# CAN-D_Rev2.net
KiCad netlist of a schematic drawn in EAGLE
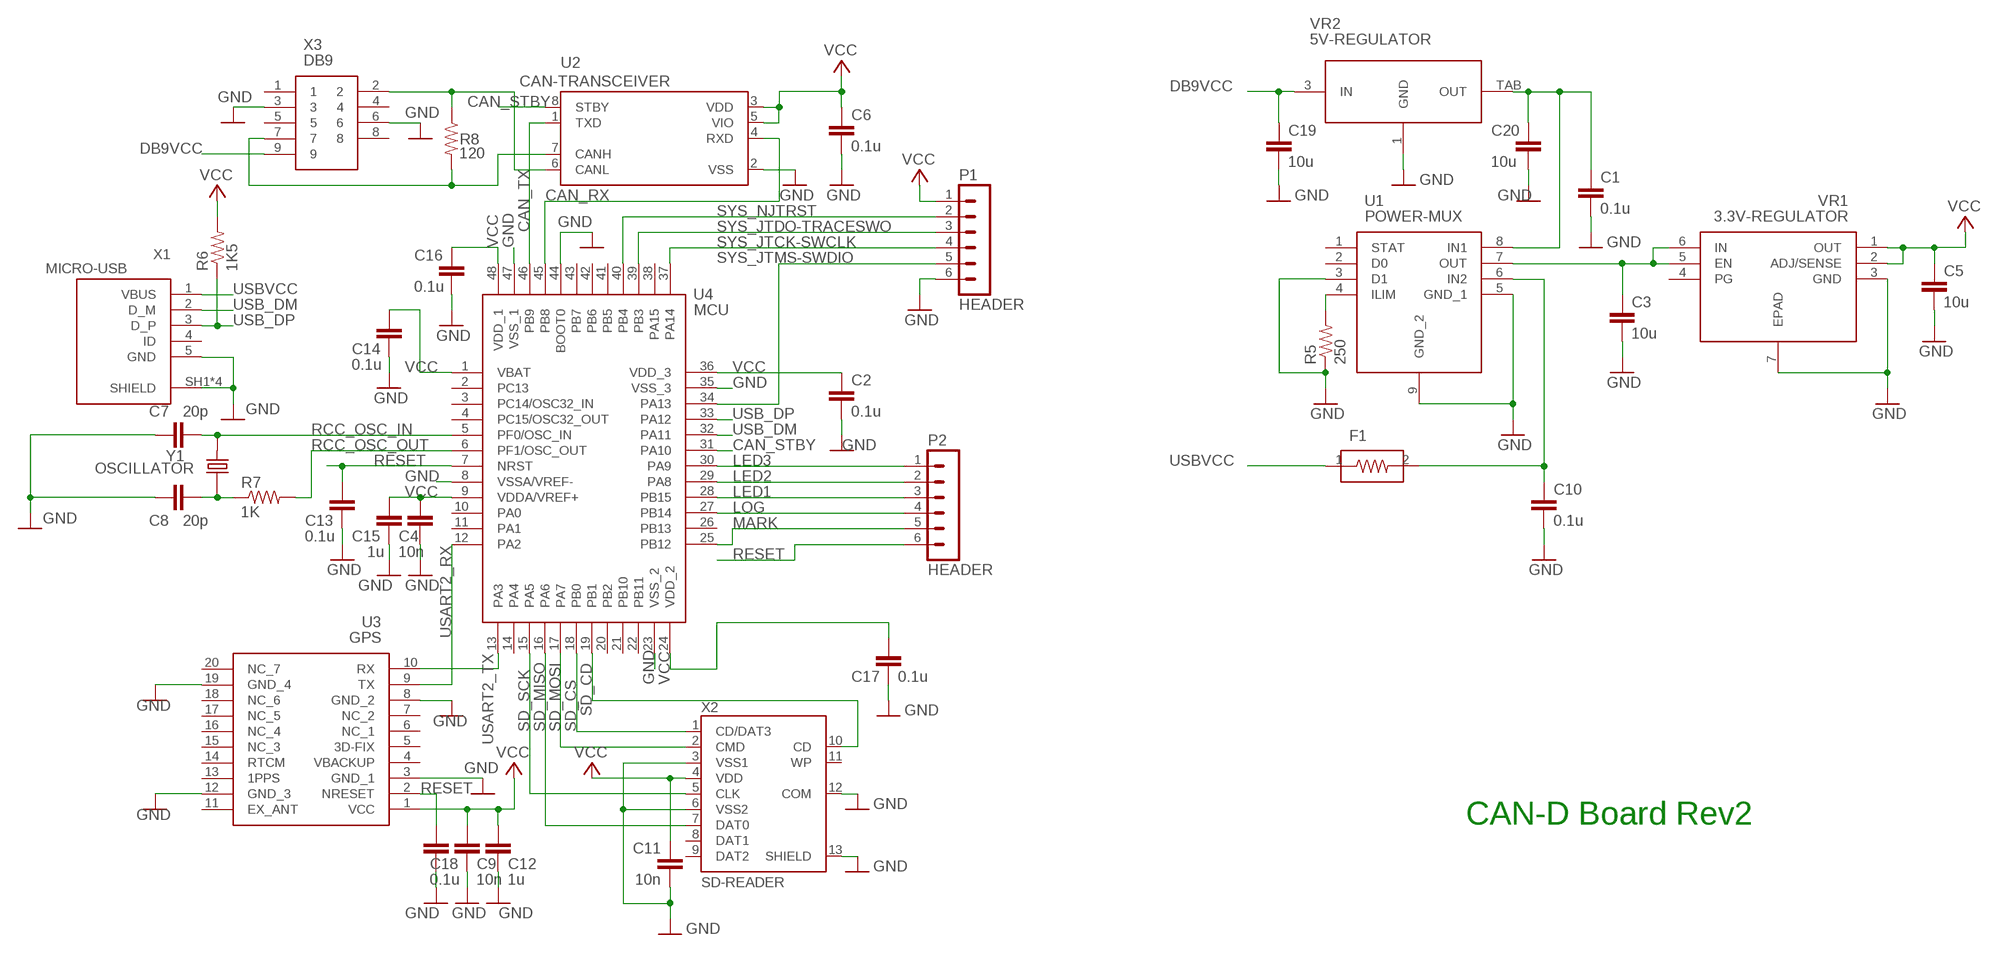
[diagram p0: schematic, sheet 1]

(export (version "E")
  (design (tool "Eeschema 10.0.6"))
  (components
    (comp (ref "C1")
      (value "0.1u")
      (footprint "eagle-import:C0603")
      (libsource (lib "eagle-import") (part "C-EUC0603"))
    )
    (comp (ref "C2")
      (value "0.1u")
      (footprint "eagle-import:C0603")
      (libsource (lib "eagle-import") (part "C-EUC0603"))
    )
    (comp (ref "C3")
      (value "10u")
      (footprint "eagle-import:C0603")
      (libsource (lib "eagle-import") (part "C-EUC0603"))
    )
    (comp (ref "C4")
      (value "10n")
      (footprint "eagle-import:C0603")
      (libsource (lib "eagle-import") (part "C-EUC0603"))
    )
    (comp (ref "C5")
      (value "10u")
      (footprint "eagle-import:C0603")
      (libsource (lib "eagle-import") (part "C-EUC0603"))
    )
    (comp (ref "C6")
      (value "0.1u")
      (footprint "eagle-import:C0603")
      (libsource (lib "eagle-import") (part "C-EUC0603"))
    )
    (comp (ref "C7")
      (value "20p")
      (footprint "eagle-import:C0603")
      (libsource (lib "eagle-import") (part "C-EUC0603"))
    )
    (comp (ref "C8")
      (value "20p")
      (footprint "eagle-import:C0603")
      (libsource (lib "eagle-import") (part "C-EUC0603"))
    )
    (comp (ref "C9")
      (value "10n")
      (footprint "eagle-import:C0603")
      (libsource (lib "eagle-import") (part "C-EUC0603"))
    )
    (comp (ref "C10")
      (value "0.1u")
      (footprint "eagle-import:C0603")
      (libsource (lib "eagle-import") (part "C-EUC0603"))
    )
    (comp (ref "C11")
      (value "10n")
      (footprint "eagle-import:C0603")
      (libsource (lib "eagle-import") (part "C-EUC0603"))
    )
    (comp (ref "C12")
      (value "1u")
      (footprint "eagle-import:C0603")
      (libsource (lib "eagle-import") (part "C-EUC0603"))
    )
    (comp (ref "C13")
      (value "0.1u")
      (footprint "eagle-import:C0603")
      (libsource (lib "eagle-import") (part "C-EUC0603"))
    )
    (comp (ref "C14")
      (value "0.1u")
      (footprint "eagle-import:C0603")
      (libsource (lib "eagle-import") (part "C-EUC0603"))
    )
    (comp (ref "C15")
      (value "1u")
      (footprint "eagle-import:C0603")
      (libsource (lib "eagle-import") (part "C-EUC0603"))
    )
    (comp (ref "C16")
      (value "0.1u")
      (footprint "eagle-import:C0603")
      (libsource (lib "eagle-import") (part "C-EUC0603"))
    )
    (comp (ref "C17")
      (value "0.1u")
      (footprint "eagle-import:C0603")
      (libsource (lib "eagle-import") (part "C-EUC0603"))
    )
    (comp (ref "C18")
      (value "0.1u")
      (footprint "eagle-import:C0603")
      (libsource (lib "eagle-import") (part "C-EUC0603"))
    )
    (comp (ref "C19")
      (value "10u")
      (footprint "eagle-import:C0603")
      (libsource (lib "eagle-import") (part "C-EUC0603"))
    )
    (comp (ref "C20")
      (value "10u")
      (footprint "eagle-import:C0603")
      (libsource (lib "eagle-import") (part "C-EUC0603"))
    )
    (comp (ref "F1")
      (value "FUSE")
      (footprint "eagle-import:0ZCJ0025FF2E")
      (fields
        (field (name "DIGI-KEY_PART_NUMBER") "507-1798-1-ND")
        (field (name "MF") "Bel Fuse")
        (field (name "MP") "0ZCJ0025FF2E")
      )
      (libsource (lib "eagle-import") (part "FUSE"))
    )
    (comp (ref "P1")
      (value "HEADER")
      (footprint "eagle-import:TSM-106-02-L-SV-P-TR")
      (libsource (lib "eagle-import") (part "HEADER"))
    )
    (comp (ref "P2")
      (value "HEADER")
      (footprint "eagle-import:TSM-106-02-L-SV-P-TR")
      (libsource (lib "eagle-import") (part "HEADER"))
    )
    (comp (ref "R5")
      (value "250")
      (footprint "eagle-import:R0603")
      (libsource (lib "eagle-import") (part "R-US_R0603"))
    )
    (comp (ref "R6")
      (value "1K5")
      (footprint "eagle-import:R0603")
      (libsource (lib "eagle-import") (part "R-US_R0603"))
    )
    (comp (ref "R7")
      (value "1K")
      (footprint "eagle-import:R0603")
      (libsource (lib "eagle-import") (part "R-US_R0603"))
    )
    (comp (ref "R8")
      (value "120")
      (footprint "eagle-import:R0603")
      (libsource (lib "eagle-import") (part "R-US_R0603"))
    )
    (comp (ref "U1")
      (value "POWER-MUX")
      (footprint "eagle-import:TPS2115ADRBR")
      (fields
        (field (name "MANUFACTURER_PART_NUMBER") "TPS2115ADRBR")
        (field (name "MOUSER_PART_NUMBER") "595-TPS2115ADRBR")
      )
      (libsource (lib "eagle-import") (part "POWER-MUX"))
    )
    (comp (ref "U2")
      (value "CAN-TRANSCEIVER")
      (footprint "eagle-import:MCP2562-E_SN")
      (fields (field (name "MF") "Microchip") (field (name "MP") "MCP2562-E/SN"))
      (libsource (lib "eagle-import") (part "CAN-TRANSCEIVER"))
    )
    (comp (ref "U3")
      (value "GPS")
      (footprint "eagle-import:FGPMMOPA6H")
      (fields (field (name "MANUFACTURER_PART_NUMBER") "FGPMMOPA6H"))
      (libsource (lib "eagle-import") (part "GPS"))
    )
    (comp (ref "U4")
      (value "MCU")
      (footprint "eagle-import:STM32F302CCT6")
      (fields
        (field (name "MANUFACTURER_PART_NUMBER") "STM32F302CCT6")
        (field (name "MOUSER_PART_NUMBER") "511-STM32F302CCT6")
        (field (name "RS_PART_NUMBER") "1656736")
      )
      (libsource (lib "eagle-import") (part "MCU"))
    )
    (comp (ref "VR1")
      (value "3.3V-REGULATOR")
      (footprint "eagle-import:LD39200PU33R")
      (fields
        (field (name "MANUFACTURER_PART_NUMBER") "LD39200PU33R")
        (field (name "MOUSER_PART_NUMBER") "511-LD39200PU33R")
      )
      (libsource (lib "eagle-import") (part "3.3V-REGULATOR"))
    )
    (comp (ref "VR2")
      (value "5V-REGULATOR")
      (footprint "eagle-import:LD1086D2T50TR")
      (fields
        (field (name "DIGI-KEY_PART_NUMBER") "497-1225-1-ND")
        (field (name "MF") "STMicroelectronics")
        (field (name "MP") "LD1086D2T50TR")
      )
      (libsource (lib "eagle-import") (part "5V-REGULATOR"))
    )
    (comp (ref "X1")
      (value "MICRO-USB")
      (footprint "eagle-import:DX4R005HJ5R2000")
      (fields
        (field (name "DIGI-KEY_PART_NUMBER") "670-2674-1-ND")
        (field (name "MF") "JAE Electronics")
        (field (name "MP") "DX4R005HJ5R2000")
      )
      (libsource (lib "eagle-import") (part "MICRO-USB"))
    )
    (comp (ref "X2")
      (value "SD-READER")
      (footprint "eagle-import:DM1AA-SF-PEJ(21)")
      (fields
        (field (name "DIGI-KEY_PART_NUMBER") "HR845CT-ND")
        (field (name "MF") "Hirose")
        (field (name "MP") "DM1AA-SF-PEJ_21_")
      )
      (libsource (lib "eagle-import") (part "SD-READER"))
    )
    (comp (ref "X3")
      (value "DB9")
      (footprint "eagle-import:1-1740195-2")
      (fields
        (field (name "MANUFACTURER_PART_NUMBER") "1-1740195-2")
        (field (name "MOUSER_PART_NUMBER") "571-1-1740195-2")
        (field (name "RS_PART_NUMBER") "5269513P")
      )
      (libsource (lib "eagle-import") (part "DB9"))
    )
    (comp (ref "Y1")
      (value "OSCILLATOR")
      (footprint "eagle-import:ABLS-8.000MHZ-B2-T")
      (fields (field (name "MF") "Abracon LLC") (field (name "MP") "ABLS-8.000MHZ-B2-T"))
      (libsource (lib "eagle-import") (part "OSCILLATOR"))
    )
  )
  (nets
    (net (code "1") (name "/CAN_RX") (class "Default")
      (node (ref "U2") (pin "4") (pinfunction "RXD_4") (pintype "output"))
      (node (ref "U4") (pin "45") (pinfunction "PB8_45") (pintype "bidirectional"))
    )
    (net (code "2") (name "/CAN_STBY") (class "Default")
      (node (ref "U2") (pin "8") (pinfunction "STBY_8") (pintype "input"))
      (node (ref "U4") (pin "31") (pinfunction "PA10_31") (pintype "bidirectional"))
    )
    (net (code "3") (name "/CAN_TX") (class "Default")
      (node (ref "U2") (pin "1") (pinfunction "TXD_1") (pintype "input"))
      (node (ref "U4") (pin "46") (pinfunction "PB9_46") (pintype "bidirectional"))
    )
    (net (code "4") (name "/DB9VCC") (class "Default")
      (node (ref "C19") (pin "1") (pinfunction "1_1") (pintype "passive"))
      (node (ref "VR2") (pin "3") (pinfunction "IN_3") (pintype "input"))
      (node (ref "X3") (pin "9") (pinfunction "9_9") (pintype "bidirectional"))
    )
    (net (code "5") (name "/LED1") (class "Default")
      (node (ref "P2") (pin "3") (pinfunction "3_3") (pintype "passive"))
      (node (ref "U4") (pin "28") (pinfunction "PB15_28") (pintype "bidirectional"))
    )
    (net (code "6") (name "/LED2") (class "Default")
      (node (ref "P2") (pin "2") (pinfunction "2_2") (pintype "passive"))
      (node (ref "U4") (pin "29") (pinfunction "PA8_29") (pintype "bidirectional"))
    )
    (net (code "7") (name "/LED3") (class "Default")
      (node (ref "P2") (pin "1") (pinfunction "1_1") (pintype "passive"))
      (node (ref "U4") (pin "30") (pinfunction "PA9_30") (pintype "bidirectional"))
    )
    (net (code "8") (name "/LOG") (class "Default")
      (node (ref "P2") (pin "4") (pinfunction "4_4") (pintype "passive"))
      (node (ref "U4") (pin "27") (pinfunction "PB14_27") (pintype "bidirectional"))
    )
    (net (code "9") (name "/MARK") (class "Default")
      (node (ref "P2") (pin "5") (pinfunction "5_5") (pintype "passive"))
      (node (ref "U4") (pin "25") (pinfunction "PB12_25") (pintype "bidirectional"))
    )
    (net (code "10") (name "/RCC_OSC_IN") (class "Default")
      (node (ref "C7") (pin "1") (pinfunction "1_1") (pintype "passive"))
      (node (ref "U4") (pin "5") (pinfunction "PF0/OSC_IN_5") (pintype "input"))
      (node (ref "Y1") (pin "2") (pinfunction "2_2") (pintype "passive"))
    )
    (net (code "11") (name "/RCC_OSC_OUT") (class "Default")
      (node (ref "R7") (pin "2") (pinfunction "2_2") (pintype "passive"))
      (node (ref "U4") (pin "6") (pinfunction "PF1/OSC_OUT_6") (pintype "output"))
    )
    (net (code "12") (name "/RESET") (class "Default")
      (node (ref "C13") (pin "1") (pinfunction "1_1") (pintype "passive"))
      (node (ref "C18") (pin "1") (pinfunction "1_1") (pintype "passive"))
      (node (ref "P2") (pin "6") (pinfunction "6_6") (pintype "passive"))
      (node (ref "U3") (pin "2") (pinfunction "NRESET_2") (pintype "bidirectional"))
      (node (ref "U4") (pin "7") (pinfunction "NRST_7") (pintype "input"))
    )
    (net (code "13") (name "/SD_CD") (class "Default")
      (node (ref "U4") (pin "19") (pinfunction "PB1_19") (pintype "bidirectional"))
      (node (ref "X2") (pin "10") (pinfunction "CD_10") (pintype "passive"))
    )
    (net (code "14") (name "/SD_CS") (class "Default")
      (node (ref "U4") (pin "18") (pinfunction "PB0_18") (pintype "bidirectional"))
      (node (ref "X2") (pin "1") (pinfunction "CD/DAT3_1") (pintype "bidirectional"))
    )
    (net (code "15") (name "/SD_MISO") (class "Default")
      (node (ref "U4") (pin "16") (pinfunction "PA6_16") (pintype "bidirectional"))
      (node (ref "X2") (pin "7") (pinfunction "DAT0_7") (pintype "bidirectional"))
    )
    (net (code "16") (name "/SD_MOSI") (class "Default")
      (node (ref "U4") (pin "17") (pinfunction "PA7_17") (pintype "bidirectional"))
      (node (ref "X2") (pin "2") (pinfunction "CMD_2") (pintype "bidirectional"))
    )
    (net (code "17") (name "/SD_SCK") (class "Default")
      (node (ref "U4") (pin "15") (pinfunction "PA5_15") (pintype "bidirectional"))
      (node (ref "X2") (pin "5") (pinfunction "CLK_5") (pintype "bidirectional"))
    )
    (net (code "18") (name "/SYS_JTCK-SWCLK") (class "Default")
      (node (ref "P1") (pin "4") (pinfunction "4_4") (pintype "passive"))
      (node (ref "U4") (pin "37") (pinfunction "PA14_37") (pintype "bidirectional"))
    )
    (net (code "19") (name "/SYS_JTDO-TRACESWO") (class "Default")
      (node (ref "P1") (pin "3") (pinfunction "3_3") (pintype "passive"))
      (node (ref "U4") (pin "39") (pinfunction "PB3_39") (pintype "bidirectional"))
    )
    (net (code "20") (name "/SYS_JTMS-SWDIO") (class "Default")
      (node (ref "P1") (pin "5") (pinfunction "5_5") (pintype "passive"))
      (node (ref "U4") (pin "34") (pinfunction "PA13_34") (pintype "bidirectional"))
    )
    (net (code "21") (name "/SYS_NJTRST") (class "Default")
      (node (ref "P1") (pin "2") (pinfunction "2_2") (pintype "passive"))
      (node (ref "U4") (pin "40") (pinfunction "PB4_40") (pintype "bidirectional"))
    )
    (net (code "22") (name "/USART2_RX") (class "Default")
      (node (ref "U3") (pin "9") (pinfunction "TX_9") (pintype "bidirectional"))
      (node (ref "U4") (pin "12") (pinfunction "PA2_12") (pintype "bidirectional"))
    )
    (net (code "23") (name "/USART2_TX") (class "Default")
      (node (ref "U3") (pin "10") (pinfunction "RX_10") (pintype "bidirectional"))
      (node (ref "U4") (pin "13") (pinfunction "PA3_13") (pintype "bidirectional"))
    )
    (net (code "24") (name "/USBVCC") (class "Default")
      (node (ref "F1") (pin "1") (pinfunction "1_1") (pintype "passive"))
      (node (ref "X1") (pin "1") (pinfunction "VBUS_1") (pintype "passive"))
    )
    (net (code "25") (name "/USB_DM") (class "Default")
      (node (ref "U4") (pin "32") (pinfunction "PA11_32") (pintype "bidirectional"))
      (node (ref "X1") (pin "2") (pinfunction "D_M_2") (pintype "passive"))
    )
    (net (code "26") (name "/USB_DP") (class "Default")
      (node (ref "R6") (pin "1") (pinfunction "1_1") (pintype "passive"))
      (node (ref "U4") (pin "33") (pinfunction "PA12_33") (pintype "bidirectional"))
      (node (ref "X1") (pin "3") (pinfunction "D_P_3") (pintype "passive"))
    )
    (net (code "27") (name "GND") (class "Default")
      (node (ref "C1") (pin "2") (pinfunction "2_2") (pintype "passive"))
      (node (ref "C10") (pin "2") (pinfunction "2_2") (pintype "passive"))
      (node (ref "C11") (pin "2") (pinfunction "2_2") (pintype "passive"))
      (node (ref "C12") (pin "2") (pinfunction "2_2") (pintype "passive"))
      (node (ref "C13") (pin "2") (pinfunction "2_2") (pintype "passive"))
      (node (ref "C14") (pin "2") (pinfunction "2_2") (pintype "passive"))
      (node (ref "C15") (pin "2") (pinfunction "2_2") (pintype "passive"))
      (node (ref "C16") (pin "2") (pinfunction "2_2") (pintype "passive"))
      (node (ref "C17") (pin "2") (pinfunction "2_2") (pintype "passive"))
      (node (ref "C18") (pin "2") (pinfunction "2_2") (pintype "passive"))
      (node (ref "C19") (pin "2") (pinfunction "2_2") (pintype "passive"))
      (node (ref "C2") (pin "2") (pinfunction "2_2") (pintype "passive"))
      (node (ref "C20") (pin "2") (pinfunction "2_2") (pintype "passive"))
      (node (ref "C3") (pin "2") (pinfunction "2_2") (pintype "passive"))
      (node (ref "C4") (pin "2") (pinfunction "2_2") (pintype "passive"))
      (node (ref "C5") (pin "2") (pinfunction "2_2") (pintype "passive"))
      (node (ref "C6") (pin "2") (pinfunction "2_2") (pintype "passive"))
      (node (ref "C7") (pin "2") (pinfunction "2_2") (pintype "passive"))
      (node (ref "C8") (pin "2") (pinfunction "2_2") (pintype "passive"))
      (node (ref "C9") (pin "2") (pinfunction "2_2") (pintype "passive"))
      (node (ref "P1") (pin "6") (pinfunction "6_6") (pintype "passive"))
      (node (ref "R5") (pin "1") (pinfunction "1_1") (pintype "passive"))
      (node (ref "U1") (pin "3") (pinfunction "D1_3") (pintype "bidirectional"))
      (node (ref "U1") (pin "5") (pinfunction "GND_1_5") (pintype "bidirectional"))
      (node (ref "U1") (pin "9") (pinfunction "GND_2_9") (pintype "bidirectional"))
      (node (ref "U2") (pin "2") (pinfunction "VSS_2") (pintype "power_in"))
      (node (ref "U3") (pin "12") (pinfunction "GND_3_12") (pintype "bidirectional"))
      (node (ref "U3") (pin "19") (pinfunction "GND_4_19") (pintype "bidirectional"))
      (node (ref "U3") (pin "3") (pinfunction "GND_1_3") (pintype "bidirectional"))
      (node (ref "U3") (pin "8") (pinfunction "GND_2_8") (pintype "bidirectional"))
      (node (ref "U4") (pin "23") (pinfunction "VSS_2_23") (pintype "power_in"))
      (node (ref "U4") (pin "35") (pinfunction "VSS_3_35") (pintype "power_in"))
      (node (ref "U4") (pin "44") (pinfunction "BOOT0_44") (pintype "bidirectional"))
      (node (ref "U4") (pin "47") (pinfunction "VSS_1_47") (pintype "power_in"))
      (node (ref "U4") (pin "8") (pinfunction "VSSA/VREF-_8") (pintype "power_in"))
      (node (ref "VR1") (pin "3") (pinfunction "GND_3") (pintype "bidirectional"))
      (node (ref "VR1") (pin "7") (pinfunction "EPAD_7") (pintype "bidirectional"))
      (node (ref "VR2") (pin "1") (pinfunction "GND_1") (pintype "passive"))
      (node (ref "X1") (pin "5") (pinfunction "GND_5") (pintype "passive"))
      (node (ref "X1") (pin "SH1") (pinfunction "SHIELD_SH1") (pintype "passive"))
      (node (ref "X1") (pin "SH2") (pinfunction "SHIELD_SH2") (pintype "passive"))
      (node (ref "X1") (pin "SH3") (pinfunction "SHIELD_SH3") (pintype "passive"))
      (node (ref "X1") (pin "SH4") (pinfunction "SHIELD_SH4") (pintype "passive"))
      (node (ref "X2") (pin "12") (pinfunction "COM_12") (pintype "passive"))
      (node (ref "X2") (pin "13") (pinfunction "SHIELD_13") (pintype "passive"))
      (node (ref "X2") (pin "3") (pinfunction "VSS1_3") (pintype "power_in"))
      (node (ref "X2") (pin "6") (pinfunction "VSS2_6") (pintype "power_in"))
      (node (ref "X3") (pin "3") (pinfunction "3_3") (pintype "bidirectional"))
      (node (ref "X3") (pin "6") (pinfunction "6_6") (pintype "bidirectional"))
    )
    (net (code "28") (name "Net-(C8-Pad1)") (class "Default")
      (node (ref "C8") (pin "1") (pinfunction "1_1") (pintype "passive"))
      (node (ref "R7") (pin "1") (pinfunction "1_1") (pintype "passive"))
      (node (ref "Y1") (pin "1") (pinfunction "1_1") (pintype "passive"))
    )
    (net (code "29") (name "Net-(U1-ILIM)") (class "Default")
      (node (ref "R5") (pin "2") (pinfunction "2_2") (pintype "passive"))
      (node (ref "U1") (pin "4") (pinfunction "ILIM_4") (pintype "bidirectional"))
    )
    (net (code "30") (name "Net-(U1-IN1)") (class "Default")
      (node (ref "C1") (pin "1") (pinfunction "1_1") (pintype "passive"))
      (node (ref "C20") (pin "1") (pinfunction "1_1") (pintype "passive"))
      (node (ref "U1") (pin "8") (pinfunction "IN1_8") (pintype "bidirectional"))
      (node (ref "VR2") (pin "TAB") (pinfunction "OUT_TAB") (pintype "output"))
    )
    (net (code "31") (name "Net-(U1-IN2)") (class "Default")
      (node (ref "C10") (pin "1") (pinfunction "1_1") (pintype "passive"))
      (node (ref "F1") (pin "2") (pinfunction "2_2") (pintype "passive"))
      (node (ref "U1") (pin "6") (pinfunction "IN2_6") (pintype "bidirectional"))
    )
    (net (code "32") (name "Net-(U1-OUT)") (class "Default")
      (node (ref "C3") (pin "1") (pinfunction "1_1") (pintype "passive"))
      (node (ref "U1") (pin "7") (pinfunction "OUT_7") (pintype "bidirectional"))
      (node (ref "VR1") (pin "5") (pinfunction "EN_5") (pintype "bidirectional"))
      (node (ref "VR1") (pin "6") (pinfunction "IN_6") (pintype "bidirectional"))
    )
    (net (code "33") (name "Net-(U2-CANH)") (class "Default")
      (node (ref "R8") (pin "2") (pinfunction "2_2") (pintype "passive"))
      (node (ref "U2") (pin "7") (pinfunction "CANH_7") (pintype "input"))
      (node (ref "X3") (pin "7") (pinfunction "7_7") (pintype "bidirectional"))
    )
    (net (code "34") (name "Net-(U2-CANL)") (class "Default")
      (node (ref "R8") (pin "1") (pinfunction "1_1") (pintype "passive"))
      (node (ref "U2") (pin "6") (pinfunction "CANL_6") (pintype "input"))
      (node (ref "X3") (pin "2") (pinfunction "2_2") (pintype "bidirectional"))
    )
    (net (code "35") (name "VCC") (class "Default")
      (node (ref "C11") (pin "1") (pinfunction "1_1") (pintype "passive"))
      (node (ref "C12") (pin "1") (pinfunction "1_1") (pintype "passive"))
      (node (ref "C14") (pin "1") (pinfunction "1_1") (pintype "passive"))
      (node (ref "C15") (pin "1") (pinfunction "1_1") (pintype "passive"))
      (node (ref "C16") (pin "1") (pinfunction "1_1") (pintype "passive"))
      (node (ref "C17") (pin "1") (pinfunction "1_1") (pintype "passive"))
      (node (ref "C2") (pin "1") (pinfunction "1_1") (pintype "passive"))
      (node (ref "C4") (pin "1") (pinfunction "1_1") (pintype "passive"))
      (node (ref "C5") (pin "1") (pinfunction "1_1") (pintype "passive"))
      (node (ref "C6") (pin "1") (pinfunction "1_1") (pintype "passive"))
      (node (ref "C9") (pin "1") (pinfunction "1_1") (pintype "passive"))
      (node (ref "P1") (pin "1") (pinfunction "1_1") (pintype "passive"))
      (node (ref "R6") (pin "2") (pinfunction "2_2") (pintype "passive"))
      (node (ref "U2") (pin "3") (pinfunction "VDD_3") (pintype "power_in"))
      (node (ref "U2") (pin "5") (pinfunction "VIO_5") (pintype "power_in"))
      (node (ref "U3") (pin "1") (pinfunction "VCC_1") (pintype "bidirectional"))
      (node (ref "U4") (pin "1") (pinfunction "VBAT_1") (pintype "bidirectional"))
      (node (ref "U4") (pin "24") (pinfunction "VDD_2_24") (pintype "power_in"))
      (node (ref "U4") (pin "36") (pinfunction "VDD_3_36") (pintype "power_in"))
      (node (ref "U4") (pin "48") (pinfunction "VDD_1_48") (pintype "power_in"))
      (node (ref "U4") (pin "9") (pinfunction "VDDA/VREF+_9") (pintype "power_in"))
      (node (ref "VR1") (pin "1") (pinfunction "OUT_1") (pintype "bidirectional"))
      (node (ref "VR1") (pin "2") (pinfunction "ADJ/SENSE_2") (pintype "bidirectional"))
      (node (ref "X2") (pin "4") (pinfunction "VDD_4") (pintype "power_in"))
    )
    (net (code "36") (name "unconnected-(U1-D0-Pad2)") (class "Default")
      (node (ref "U1") (pin "2") (pinfunction "D0_2") (pintype "bidirectional"))
    )
    (net (code "37") (name "unconnected-(U1-STAT-Pad1)") (class "Default")
      (node (ref "U1") (pin "1") (pinfunction "STAT_1") (pintype "bidirectional"))
    )
    (net (code "38") (name "unconnected-(U3-1PPS-Pad13)") (class "Default")
      (node (ref "U3") (pin "13") (pinfunction "1PPS_13") (pintype "bidirectional"))
    )
    (net (code "39") (name "unconnected-(U3-3D-FIX-Pad5)") (class "Default")
      (node (ref "U3") (pin "5") (pinfunction "3D-FIX_5") (pintype "bidirectional"))
    )
    (net (code "40") (name "unconnected-(U3-EX_ANT-Pad11)") (class "Default")
      (node (ref "U3") (pin "11") (pinfunction "EX_ANT_11") (pintype "bidirectional"))
    )
    (net (code "41") (name "unconnected-(U3-NC_1-Pad6)") (class "Default")
      (node (ref "U3") (pin "6") (pinfunction "NC_1_6") (pintype "bidirectional"))
    )
    (net (code "42") (name "unconnected-(U3-NC_2-Pad7)") (class "Default")
      (node (ref "U3") (pin "7") (pinfunction "NC_2_7") (pintype "bidirectional"))
    )
    (net (code "43") (name "unconnected-(U3-NC_3-Pad15)") (class "Default")
      (node (ref "U3") (pin "15") (pinfunction "NC_3_15") (pintype "bidirectional"))
    )
    (net (code "44") (name "unconnected-(U3-NC_4-Pad16)") (class "Default")
      (node (ref "U3") (pin "16") (pinfunction "NC_4_16") (pintype "bidirectional"))
    )
    (net (code "45") (name "unconnected-(U3-NC_5-Pad17)") (class "Default")
      (node (ref "U3") (pin "17") (pinfunction "NC_5_17") (pintype "bidirectional"))
    )
    (net (code "46") (name "unconnected-(U3-NC_6-Pad18)") (class "Default")
      (node (ref "U3") (pin "18") (pinfunction "NC_6_18") (pintype "bidirectional"))
    )
    (net (code "47") (name "unconnected-(U3-NC_7-Pad20)") (class "Default")
      (node (ref "U3") (pin "20") (pinfunction "NC_7_20") (pintype "bidirectional"))
    )
    (net (code "48") (name "unconnected-(U3-RTCM-Pad14)") (class "Default")
      (node (ref "U3") (pin "14") (pinfunction "RTCM_14") (pintype "bidirectional"))
    )
    (net (code "49") (name "unconnected-(U3-VBACKUP-Pad4)") (class "Default")
      (node (ref "U3") (pin "4") (pinfunction "VBACKUP_4") (pintype "bidirectional"))
    )
    (net (code "50") (name "unconnected-(U4-PA0-Pad10)") (class "Default")
      (node (ref "U4") (pin "10") (pinfunction "PA0_10") (pintype "bidirectional"))
    )
    (net (code "51") (name "unconnected-(U4-PA1-Pad11)") (class "Default")
      (node (ref "U4") (pin "11") (pinfunction "PA1_11") (pintype "bidirectional"))
    )
    (net (code "52") (name "unconnected-(U4-PA4-Pad14)") (class "Default")
      (node (ref "U4") (pin "14") (pinfunction "PA4_14") (pintype "bidirectional"))
    )
    (net (code "53") (name "unconnected-(U4-PA15-Pad38)") (class "Default")
      (node (ref "U4") (pin "38") (pinfunction "PA15_38") (pintype "bidirectional"))
    )
    (net (code "54") (name "unconnected-(U4-PB2-Pad20)") (class "Default")
      (node (ref "U4") (pin "20") (pinfunction "PB2_20") (pintype "bidirectional"))
    )
    (net (code "55") (name "unconnected-(U4-PB5-Pad41)") (class "Default")
      (node (ref "U4") (pin "41") (pinfunction "PB5_41") (pintype "bidirectional"))
    )
    (net (code "56") (name "unconnected-(U4-PB6-Pad42)") (class "Default")
      (node (ref "U4") (pin "42") (pinfunction "PB6_42") (pintype "bidirectional"))
    )
    (net (code "57") (name "unconnected-(U4-PB7-Pad43)") (class "Default")
      (node (ref "U4") (pin "43") (pinfunction "PB7_43") (pintype "bidirectional"))
    )
    (net (code "58") (name "unconnected-(U4-PB10-Pad21)") (class "Default")
      (node (ref "U4") (pin "21") (pinfunction "PB10_21") (pintype "bidirectional"))
    )
    (net (code "59") (name "unconnected-(U4-PB11-Pad22)") (class "Default")
      (node (ref "U4") (pin "22") (pinfunction "PB11_22") (pintype "bidirectional"))
    )
    (net (code "60") (name "unconnected-(U4-PB13-Pad26)") (class "Default")
      (node (ref "U4") (pin "26") (pinfunction "PB13_26") (pintype "bidirectional"))
    )
    (net (code "61") (name "unconnected-(U4-PC13-Pad2)") (class "Default")
      (node (ref "U4") (pin "2") (pinfunction "PC13_2") (pintype "bidirectional"))
    )
    (net (code "62") (name "unconnected-(U4-PC14{slash}OSC32_IN-Pad3)") (class "Default")
      (node (ref "U4") (pin "3") (pinfunction "PC14/OSC32_IN_3") (pintype "input"))
    )
    (net (code "63") (name "unconnected-(U4-PC15{slash}OSC32_OUT-Pad4)") (class "Default")
      (node (ref "U4") (pin "4") (pinfunction "PC15/OSC32_OUT_4") (pintype "output"))
    )
    (net (code "64") (name "unconnected-(VR1-PG-Pad4)") (class "Default")
      (node (ref "VR1") (pin "4") (pinfunction "PG_4") (pintype "bidirectional"))
    )
    (net (code "65") (name "unconnected-(X1-ID-Pad4)") (class "Default")
      (node (ref "X1") (pin "4") (pinfunction "ID_4") (pintype "passive"))
    )
    (net (code "66") (name "unconnected-(X2-DAT1-Pad8)") (class "Default")
      (node (ref "X2") (pin "8") (pinfunction "DAT1_8") (pintype "bidirectional"))
    )
    (net (code "67") (name "unconnected-(X2-DAT2-Pad9)") (class "Default")
      (node (ref "X2") (pin "9") (pinfunction "DAT2_9") (pintype "bidirectional"))
    )
    (net (code "68") (name "unconnected-(X2-WP-Pad11)") (class "Default")
      (node (ref "X2") (pin "11") (pinfunction "WP_11") (pintype "passive"))
    )
    (net (code "69") (name "unconnected-(X3-Pad1)") (class "Default")
      (node (ref "X3") (pin "1") (pinfunction "1_1") (pintype "bidirectional"))
    )
    (net (code "70") (name "unconnected-(X3-Pad4)") (class "Default")
      (node (ref "X3") (pin "4") (pinfunction "4_4") (pintype "bidirectional"))
    )
    (net (code "71") (name "unconnected-(X3-Pad5)") (class "Default")
      (node (ref "X3") (pin "5") (pinfunction "5_5") (pintype "bidirectional"))
    )
    (net (code "72") (name "unconnected-(X3-Pad8)") (class "Default")
      (node (ref "X3") (pin "8") (pinfunction "8_8") (pintype "bidirectional"))
    )
  )
)
